# led.net
KiCad netlist of a schematic drawn in Altium Designer
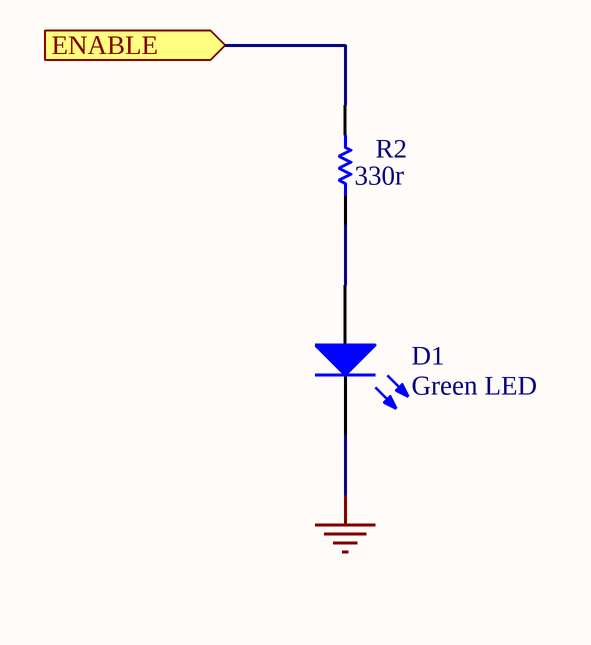
[diagram p0: led.SchDoc]

(export (version "E")
  (design (tool "Eeschema 10.0.6"))
  (components
    (comp (ref "D1")
      (value "Green LED")
      (footprint "LED-0")
      (description "Typical INFRARED GaAs LED")
      (fields (field (name "PUBLISHER") "Altium Limited"))
      (libsource (lib "Miscellaneous Devices") (part "LED0"))
    )
    (comp (ref "R2")
      (value "330r")
      (footprint "AXIAL-0.3")
      (description "Resistor")
      (fields (field (name "PUBLISHER") "Altium Limited"))
      (libsource (lib "Miscellaneous Devices") (part "Res1"))
    )
  )
  (nets
    (net (code "1") (name "/ENABLE") (class "Default")
      (node (ref "R2") (pin "2") (pinfunction "2_2") (pintype "passive"))
    )
    (net (code "2") (name "Gnd") (class "Default")
      (node (ref "D1") (pin "2") (pinfunction "K_2") (pintype "passive"))
    )
    (net (code "3") (name "Net-(D1-A)") (class "Default")
      (node (ref "D1") (pin "1") (pinfunction "A_1") (pintype "passive"))
      (node (ref "R2") (pin "1") (pinfunction "1_1") (pintype "passive"))
    )
  )
)
